# Altium.net
KiCad netlist of a schematic drawn in Altium Designer
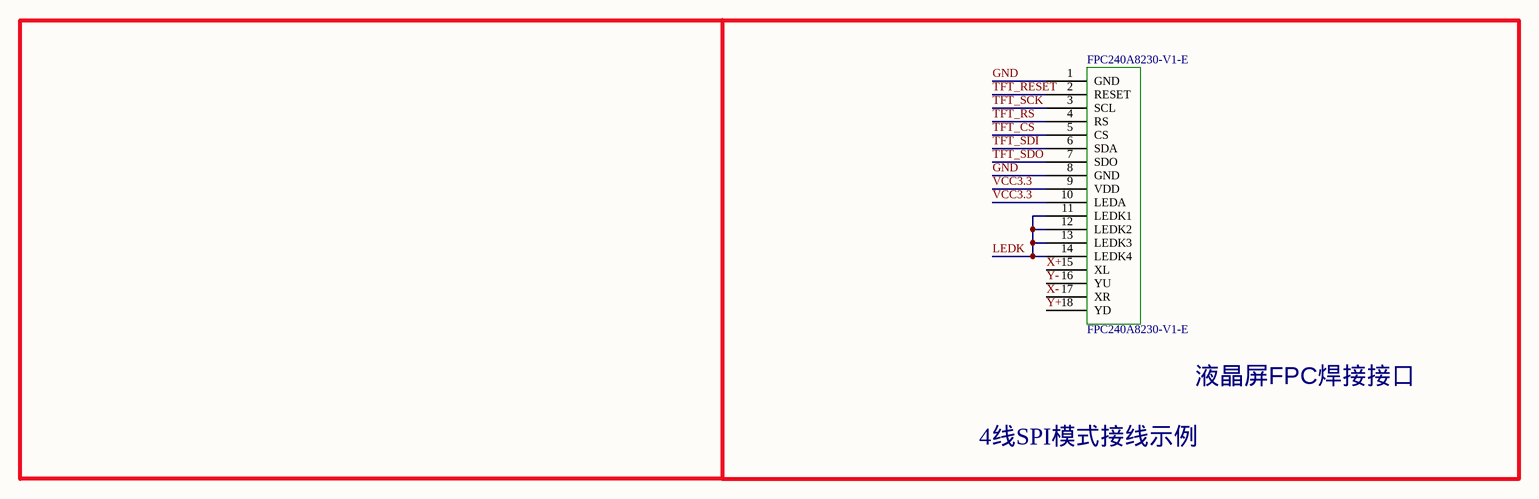
[diagram p0: 原理图(Altium).SchDoc]

(export (version "E")
  (design (tool "Eeschema 10.0.6"))
  (components
    (comp (ref "FPC240A8230-V1-E")
      (value "FPC240A8230-V1-E")
      (footprint "FPC240A8230-V1-E")
      (libsource (lib "Schlib1") (part "FPC240A8230-V1-E"))
    )
  )
  (nets
    (net (code "1") (name "/GND") (class "Default")
      (node (ref "FPC240A8230-V1-E") (pin "1") (pinfunction "GND_1") (pintype "passive"))
      (node (ref "FPC240A8230-V1-E") (pin "8") (pinfunction "GND_8") (pintype "passive"))
    )
    (net (code "2") (name "/LEDK") (class "Default")
      (node (ref "FPC240A8230-V1-E") (pin "11") (pinfunction "LEDK1_11") (pintype "passive"))
      (node (ref "FPC240A8230-V1-E") (pin "12") (pinfunction "LEDK2_12") (pintype "passive"))
      (node (ref "FPC240A8230-V1-E") (pin "13") (pinfunction "LEDK3_13") (pintype "passive"))
      (node (ref "FPC240A8230-V1-E") (pin "14") (pinfunction "LEDK4_14") (pintype "passive"))
    )
    (net (code "3") (name "/TFT_CS") (class "Default")
      (node (ref "FPC240A8230-V1-E") (pin "5") (pinfunction "CS_5") (pintype "passive"))
    )
    (net (code "4") (name "/TFT_RESET") (class "Default")
      (node (ref "FPC240A8230-V1-E") (pin "2") (pinfunction "RESET_2") (pintype "passive"))
    )
    (net (code "5") (name "/TFT_RS") (class "Default")
      (node (ref "FPC240A8230-V1-E") (pin "4") (pinfunction "RS_4") (pintype "passive"))
    )
    (net (code "6") (name "/TFT_SCK") (class "Default")
      (node (ref "FPC240A8230-V1-E") (pin "3") (pinfunction "SCL_3") (pintype "passive"))
    )
    (net (code "7") (name "/TFT_SDI") (class "Default")
      (node (ref "FPC240A8230-V1-E") (pin "6") (pinfunction "SDA_6") (pintype "passive"))
    )
    (net (code "8") (name "/TFT_SDO") (class "Default")
      (node (ref "FPC240A8230-V1-E") (pin "7") (pinfunction "SDO_7") (pintype "passive"))
    )
    (net (code "9") (name "/VCC3.3") (class "Default")
      (node (ref "FPC240A8230-V1-E") (pin "10") (pinfunction "LEDA_10") (pintype "passive"))
      (node (ref "FPC240A8230-V1-E") (pin "9") (pinfunction "VDD_9") (pintype "passive"))
    )
    (net (code "10") (name "/X+") (class "Default")
      (node (ref "FPC240A8230-V1-E") (pin "15") (pinfunction "XL_15") (pintype "passive"))
    )
    (net (code "11") (name "/X-") (class "Default")
      (node (ref "FPC240A8230-V1-E") (pin "17") (pinfunction "XR_17") (pintype "passive"))
    )
    (net (code "12") (name "/Y+") (class "Default")
      (node (ref "FPC240A8230-V1-E") (pin "18") (pinfunction "YD_18") (pintype "passive"))
    )
    (net (code "13") (name "/Y-") (class "Default")
      (node (ref "FPC240A8230-V1-E") (pin "16") (pinfunction "YU_16") (pintype "passive"))
    )
  )
)
